# avr-micro-usb.net
KiCad netlist of a schematic drawn in EAGLE
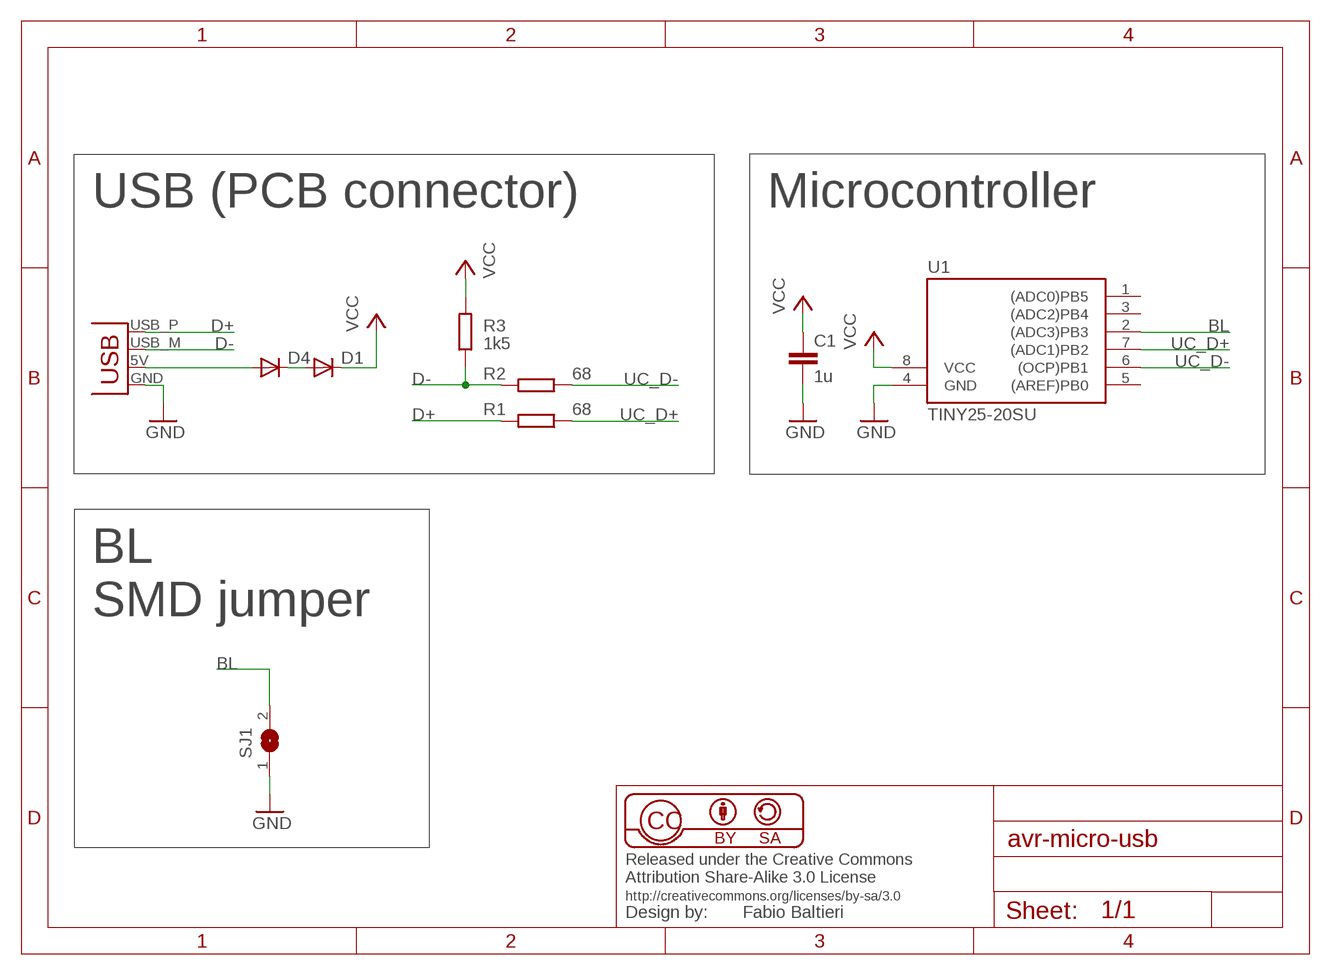
[diagram p0: schematic, sheet 1]

(export (version "E")
  (design (tool "Eeschema 10.0.6"))
  (components
    (comp (ref "C1")
      (value "1u")
      (footprint "eagle-import:C0805")
      (libsource (lib "eagle-import") (part "C-EUC0805"))
    )
    (comp (ref "D1")
      (value "DIODE-MINIMELF")
      (footprint "eagle-import:MINIMELF")
      (libsource (lib "eagle-import") (part "DIODE-MINIMELF"))
    )
    (comp (ref "D4")
      (value "DIODE-MINIMELF")
      (footprint "eagle-import:MINIMELF")
      (libsource (lib "eagle-import") (part "DIODE-MINIMELF"))
    )
    (comp (ref "R1")
      (value "68")
      (footprint "eagle-import:R0603")
      (libsource (lib "eagle-import") (part "R-EU_R0603"))
    )
    (comp (ref "R2")
      (value "68")
      (footprint "eagle-import:R0603")
      (libsource (lib "eagle-import") (part "R-EU_R0603"))
    )
    (comp (ref "R3")
      (value "1k5")
      (footprint "eagle-import:R0603")
      (libsource (lib "eagle-import") (part "R-EU_R0603"))
    )
    (comp (ref "SJ1") (value "SJ") (footprint "eagle-import:SJ") (libsource (lib "eagle-import") (part "SJ")))
    (comp (ref "U1")
      (value "TINY25-20SU")
      (footprint "eagle-import:SOIC8")
      (libsource (lib "eagle-import") (part "TINY25-20SU"))
    )
    (comp (ref "X1")
      (value "USBPCB")
      (footprint "eagle-import:USB-A-PCB")
      (libsource (lib "eagle-import") (part "USBPCB"))
    )
  )
  (nets
    (net (code "1") (name "/BL") (class "Default")
      (node (ref "SJ1") (pin "2") (pinfunction "2_2") (pintype "passive"))
      (node (ref "U1") (pin "2") (pinfunction "(ADC3)PB3_2") (pintype "bidirectional"))
    )
    (net (code "2") (name "/D+") (class "Default")
      (node (ref "R1") (pin "2") (pinfunction "2_2") (pintype "passive"))
      (node (ref "X1") (pin "USB_P") (pinfunction "D+_USB_P") (pintype "bidirectional"))
    )
    (net (code "3") (name "/D-") (class "Default")
      (node (ref "R2") (pin "2") (pinfunction "2_2") (pintype "passive"))
      (node (ref "R3") (pin "1") (pinfunction "1_1") (pintype "passive"))
      (node (ref "X1") (pin "USB_M") (pinfunction "D-_USB_M") (pintype "bidirectional"))
    )
    (net (code "4") (name "/UC_D+") (class "Default")
      (node (ref "R1") (pin "1") (pinfunction "1_1") (pintype "passive"))
      (node (ref "U1") (pin "7") (pinfunction "(ADC1)PB2_7") (pintype "bidirectional"))
    )
    (net (code "5") (name "/UC_D-") (class "Default")
      (node (ref "R2") (pin "1") (pinfunction "1_1") (pintype "passive"))
      (node (ref "U1") (pin "6") (pinfunction "(OCP)PB1_6") (pintype "bidirectional"))
    )
    (net (code "6") (name "GND") (class "Default")
      (node (ref "C1") (pin "2") (pinfunction "2_2") (pintype "passive"))
      (node (ref "SJ1") (pin "1") (pinfunction "1_1") (pintype "passive"))
      (node (ref "U1") (pin "4") (pinfunction "GND_4") (pintype "power_in"))
      (node (ref "X1") (pin "GND") (pinfunction "GND_GND") (pintype "bidirectional"))
    )
    (net (code "7") (name "Net-(D1-PadA)") (class "Default")
      (node (ref "D1") (pin "A") (pinfunction "A_A") (pintype "passive"))
      (node (ref "D4") (pin "C") (pinfunction "C_C") (pintype "passive"))
    )
    (net (code "8") (name "Net-(X1-VBUS)") (class "Default")
      (node (ref "D4") (pin "A") (pinfunction "A_A") (pintype "passive"))
      (node (ref "X1") (pin "5V") (pinfunction "VBUS_5V") (pintype "bidirectional"))
    )
    (net (code "9") (name "VCC") (class "Default")
      (node (ref "C1") (pin "1") (pinfunction "1_1") (pintype "passive"))
      (node (ref "D1") (pin "C") (pinfunction "C_C") (pintype "passive"))
      (node (ref "R3") (pin "2") (pinfunction "2_2") (pintype "passive"))
      (node (ref "U1") (pin "8") (pinfunction "VCC_8") (pintype "power_in"))
    )
    (net (code "10") (name "unconnected-(U1-(ADC0)PB5-Pad1)") (class "Default")
      (node (ref "U1") (pin "1") (pinfunction "(ADC0)PB5_1") (pintype "bidirectional"))
    )
    (net (code "11") (name "unconnected-(U1-(ADC2)PB4-Pad3)") (class "Default")
      (node (ref "U1") (pin "3") (pinfunction "(ADC2)PB4_3") (pintype "bidirectional"))
    )
    (net (code "12") (name "unconnected-(U1-(AREF)PB0-Pad5)") (class "Default")
      (node (ref "U1") (pin "5") (pinfunction "(AREF)PB0_5") (pintype "bidirectional"))
    )
  )
)
